# 3_circuito_logico_AND.net
KiCad netlist of a schematic drawn in EasyEDA Pro
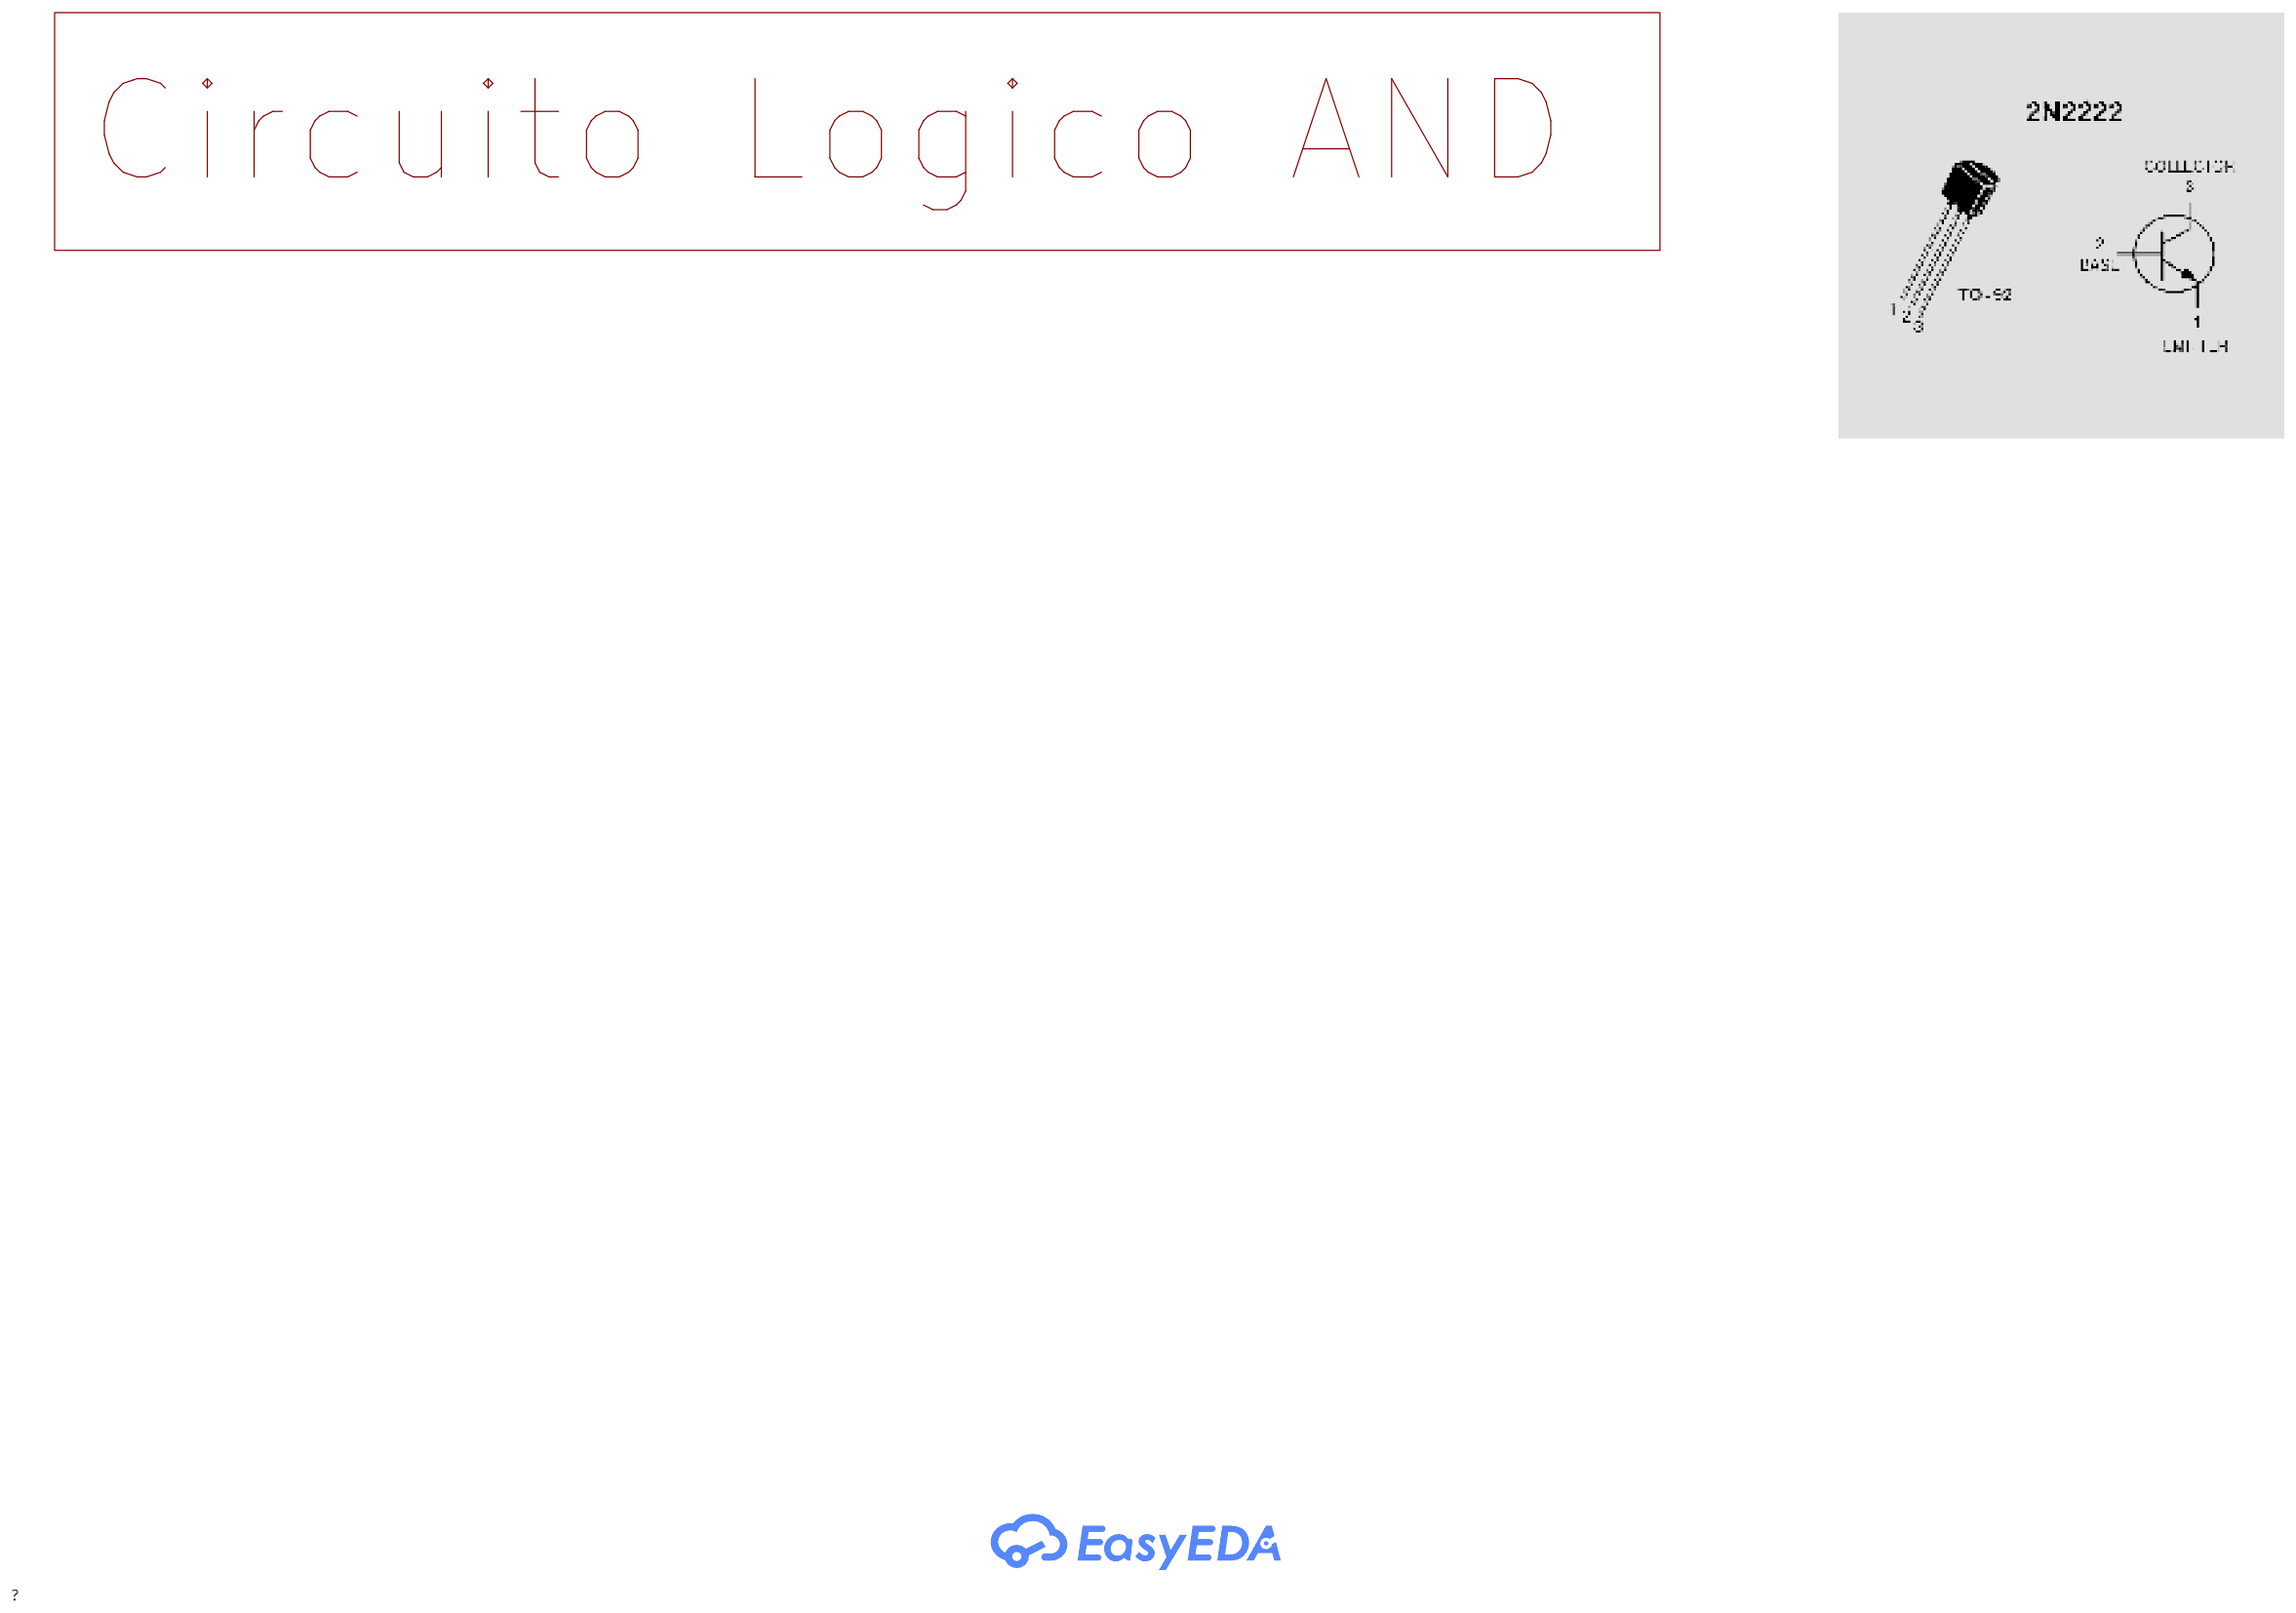
[diagram p0: P1]
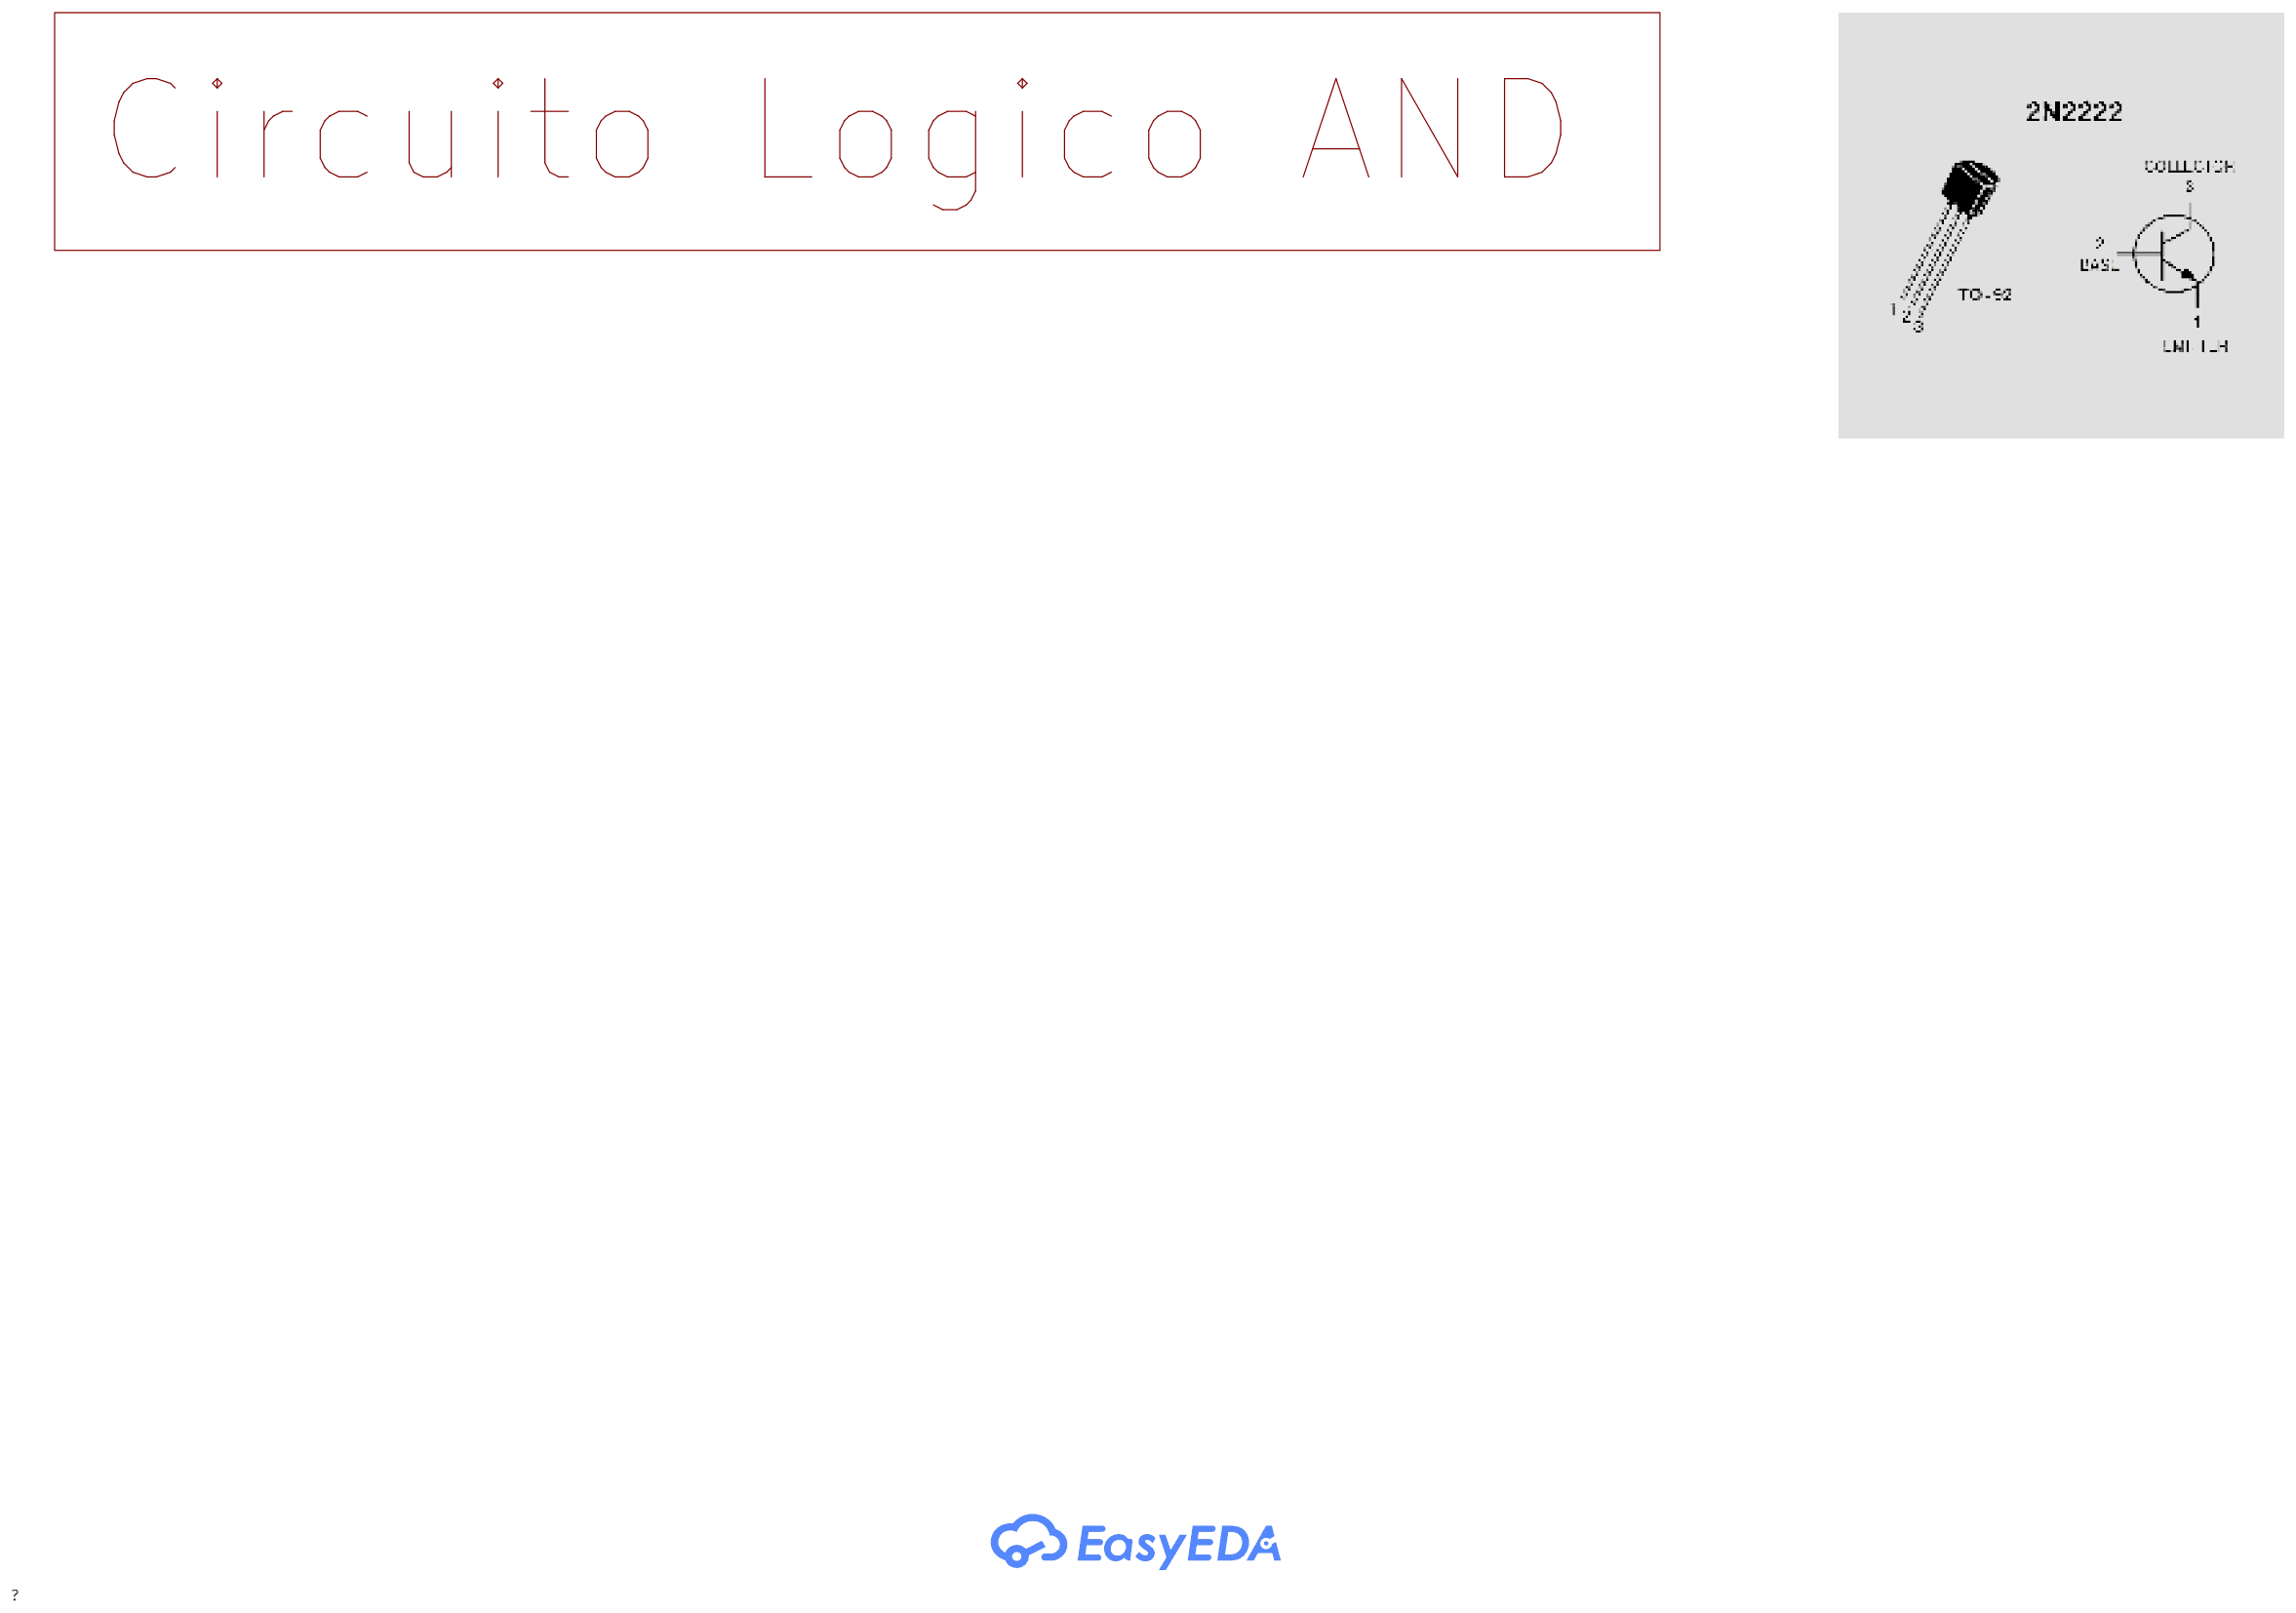
[diagram p1: P2]
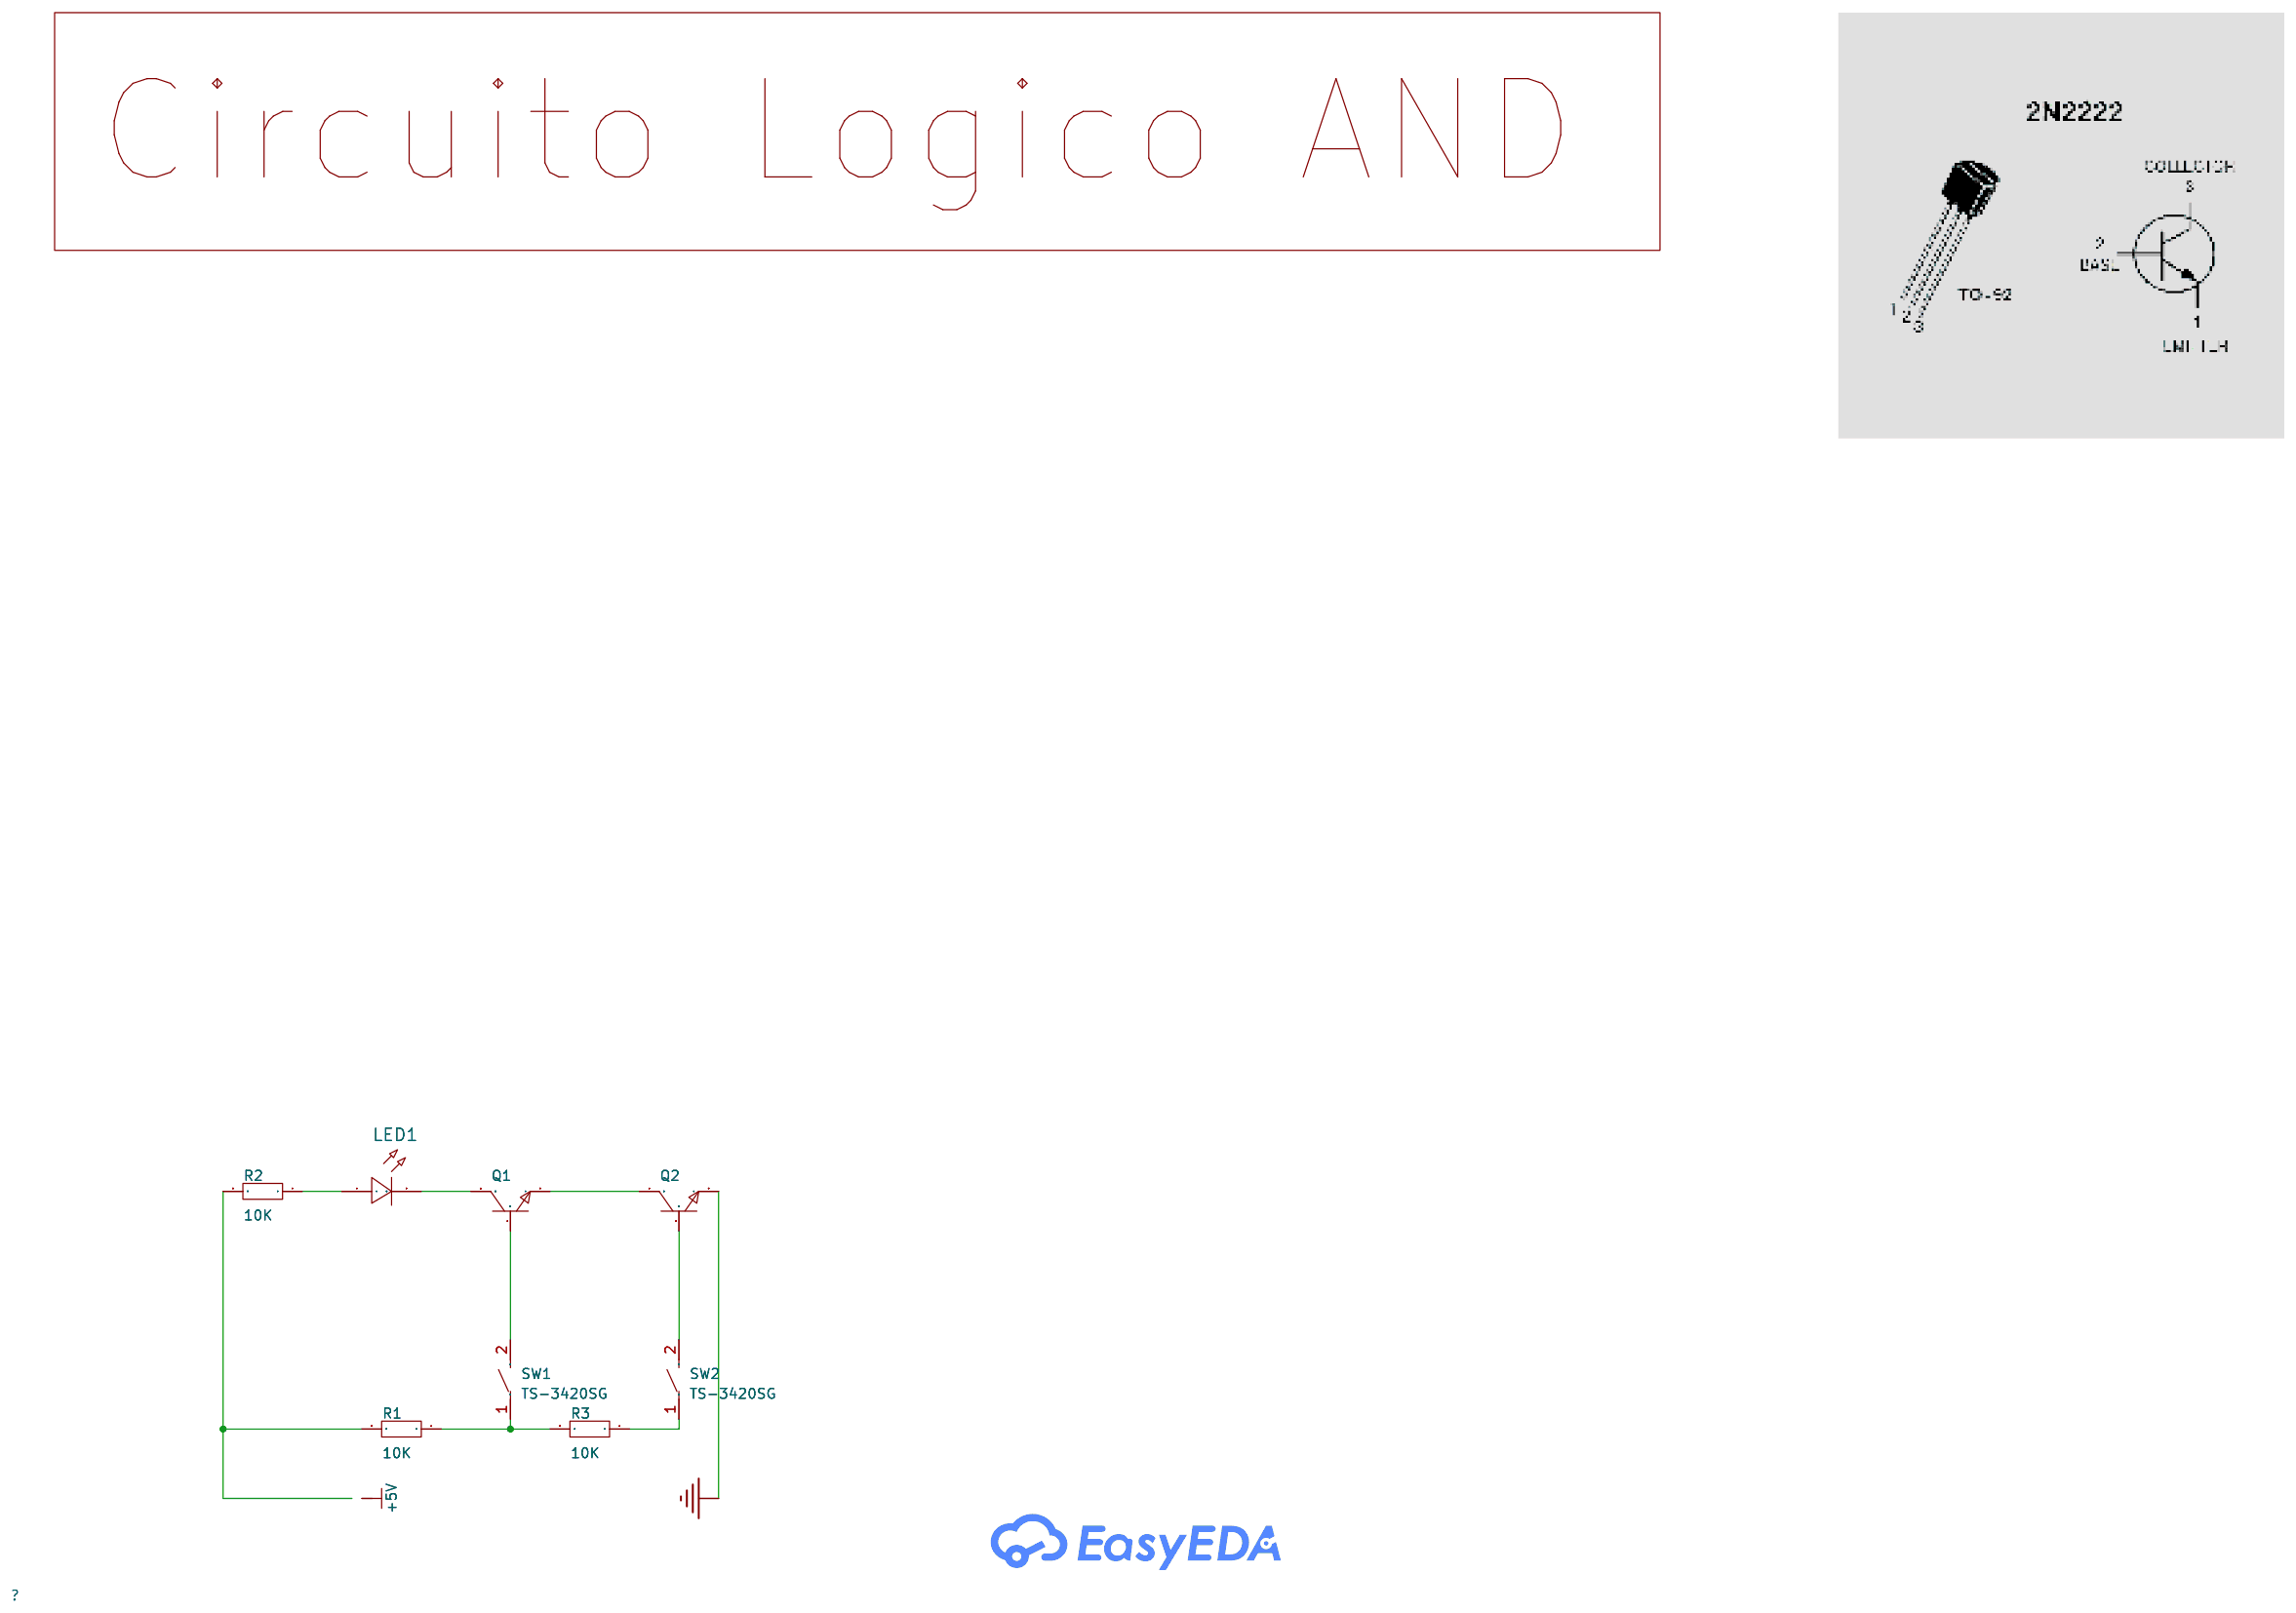
[diagram p2: P3]
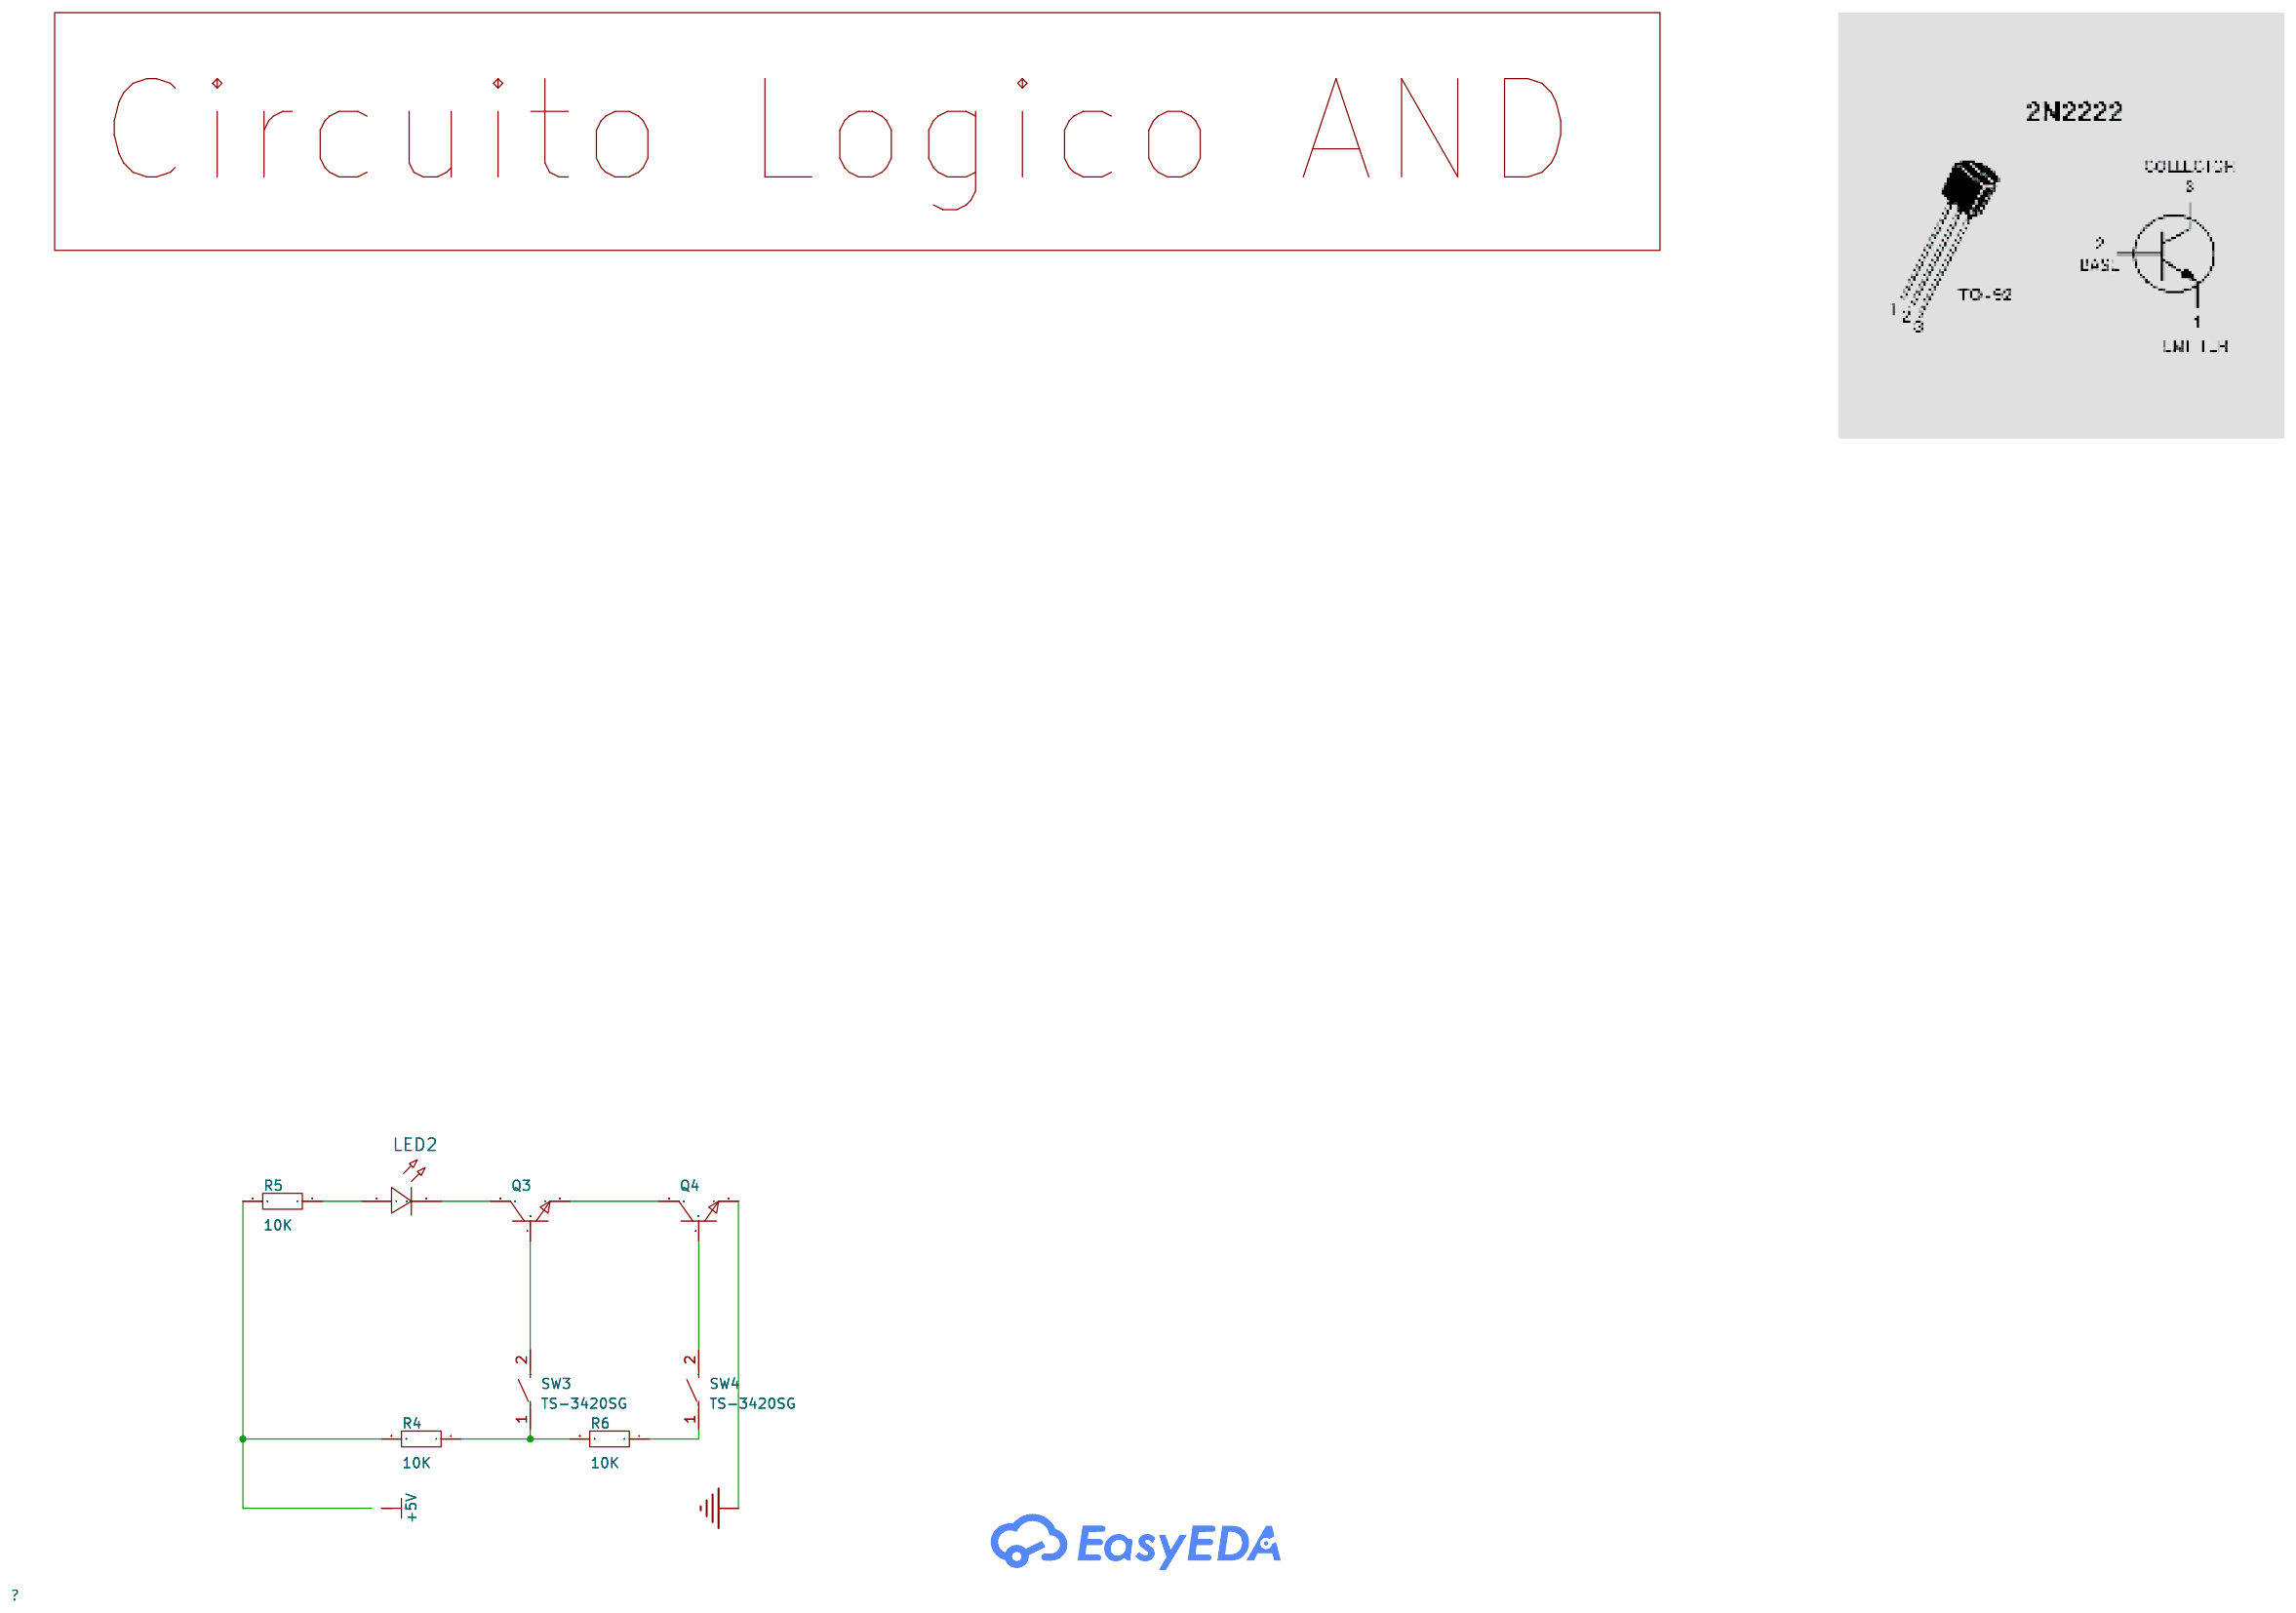
[diagram p3: P4]
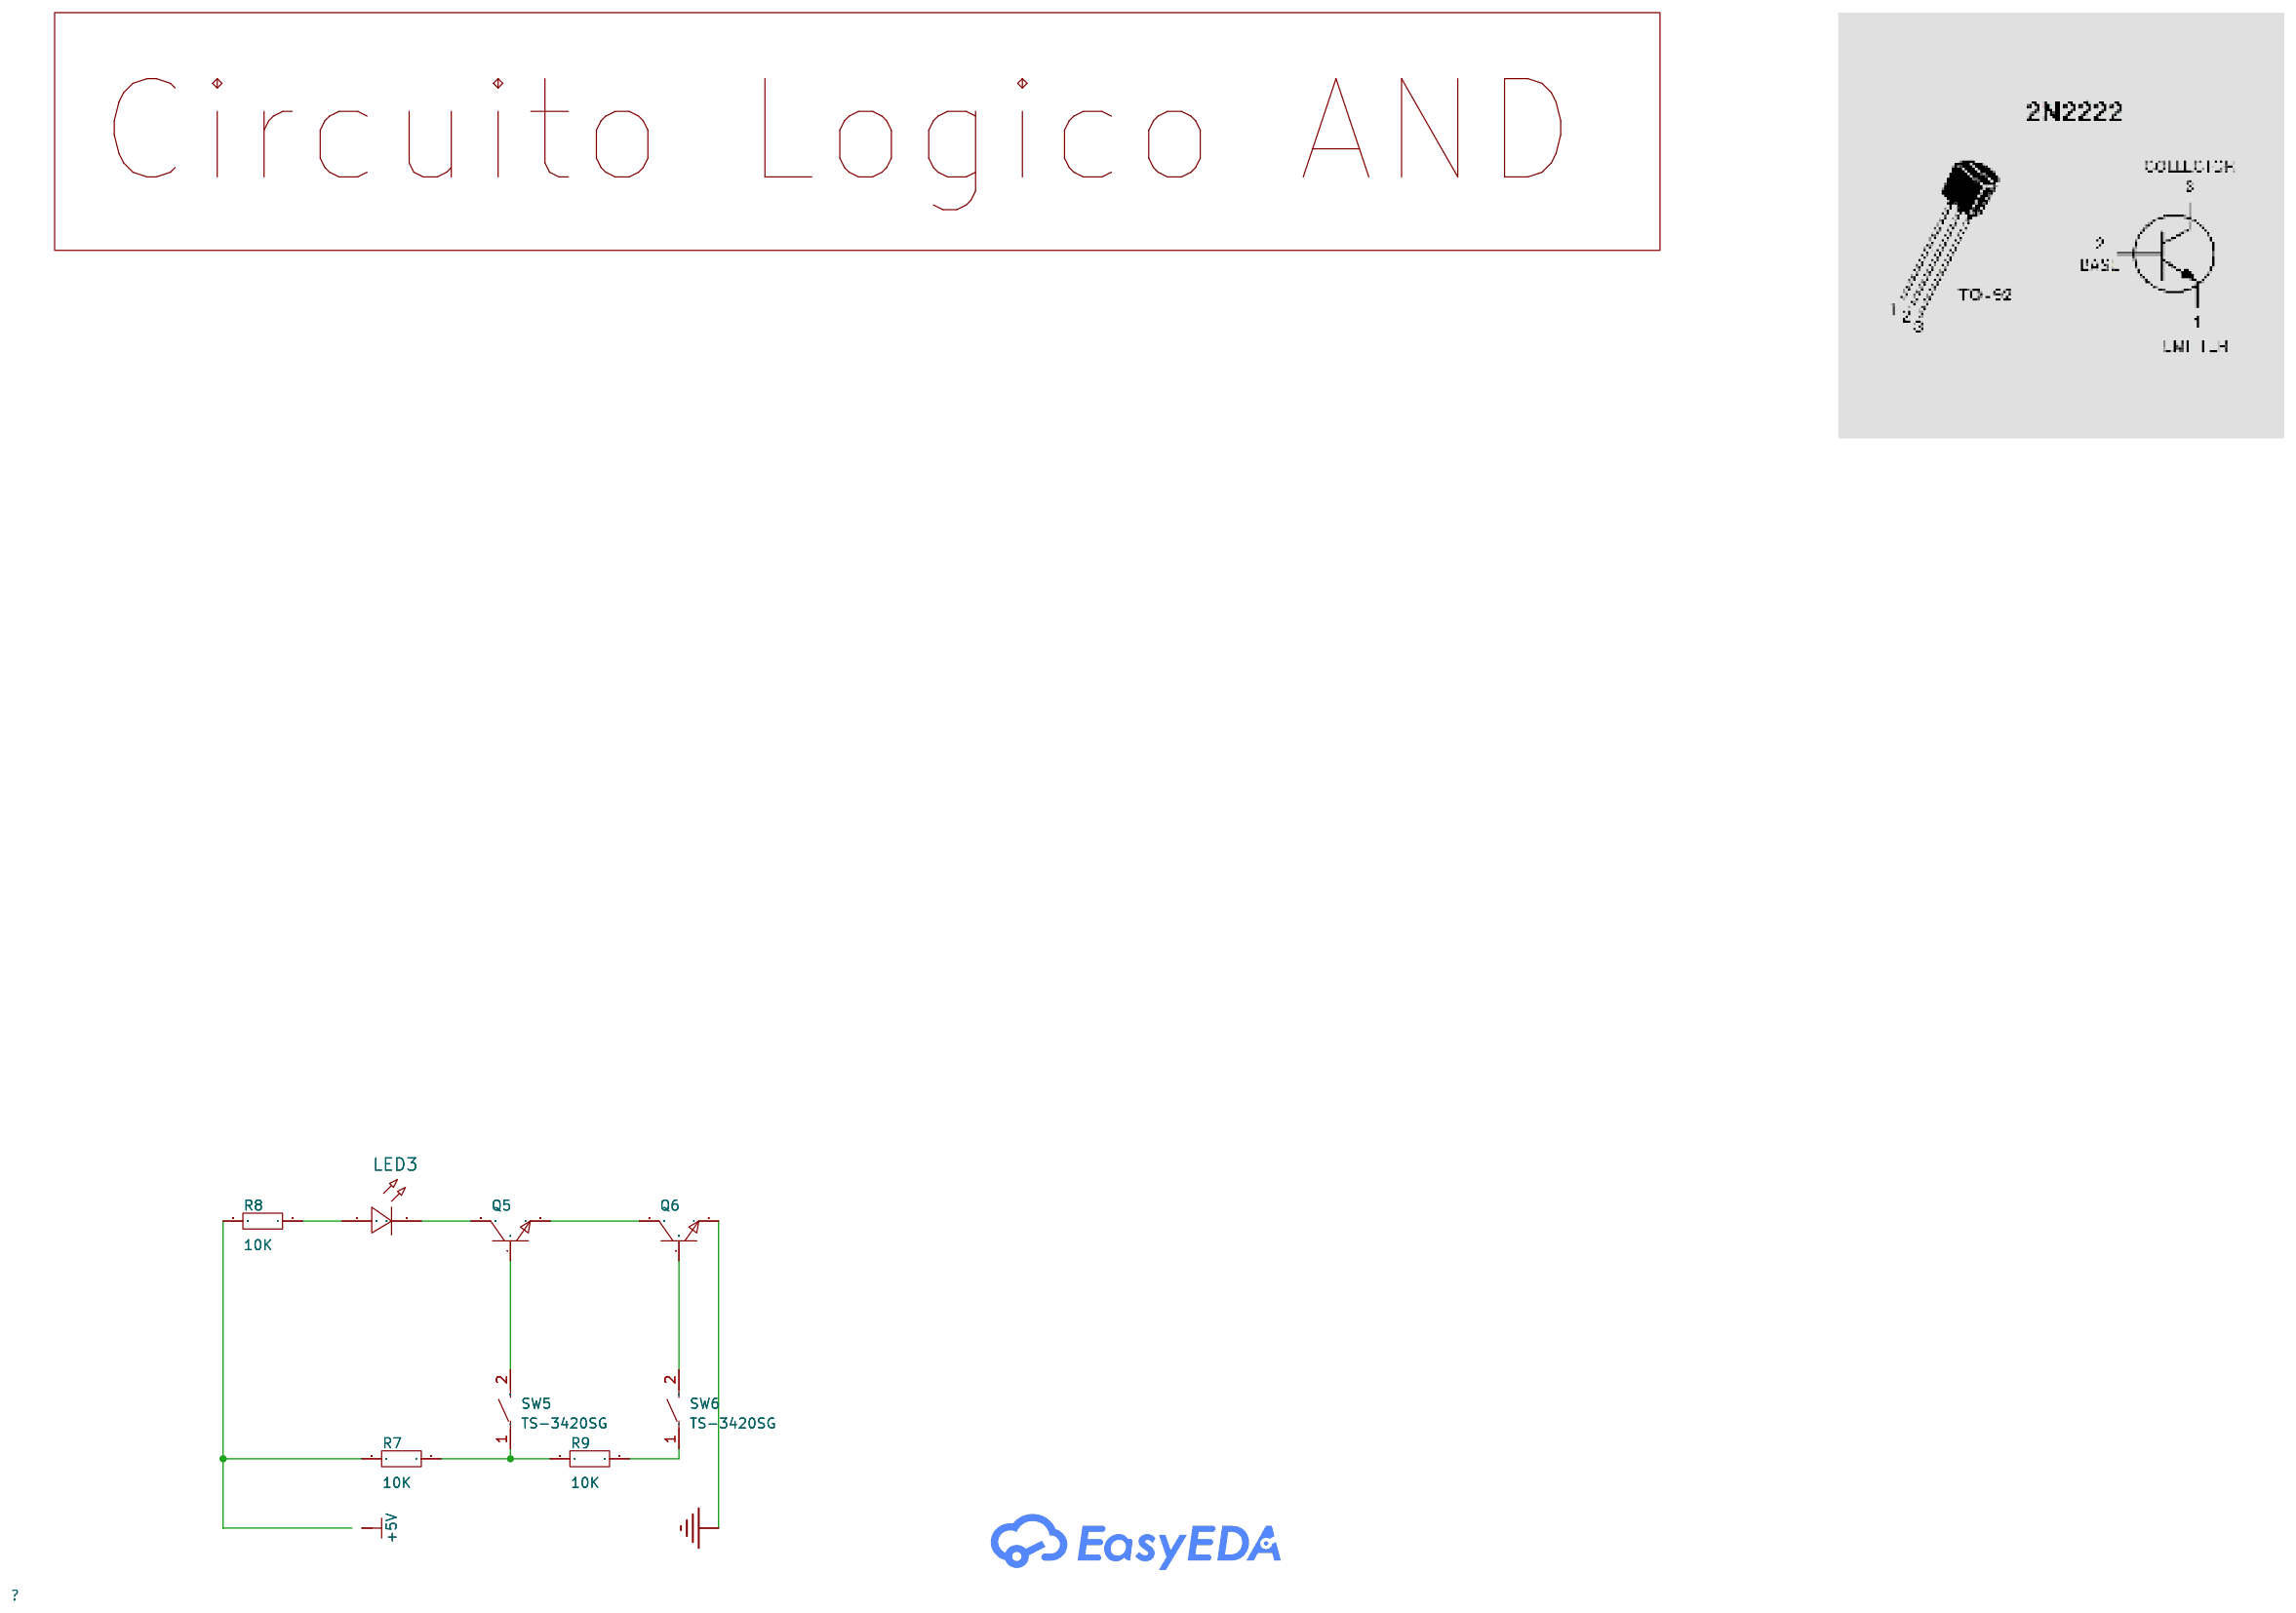
[diagram p4: P7]
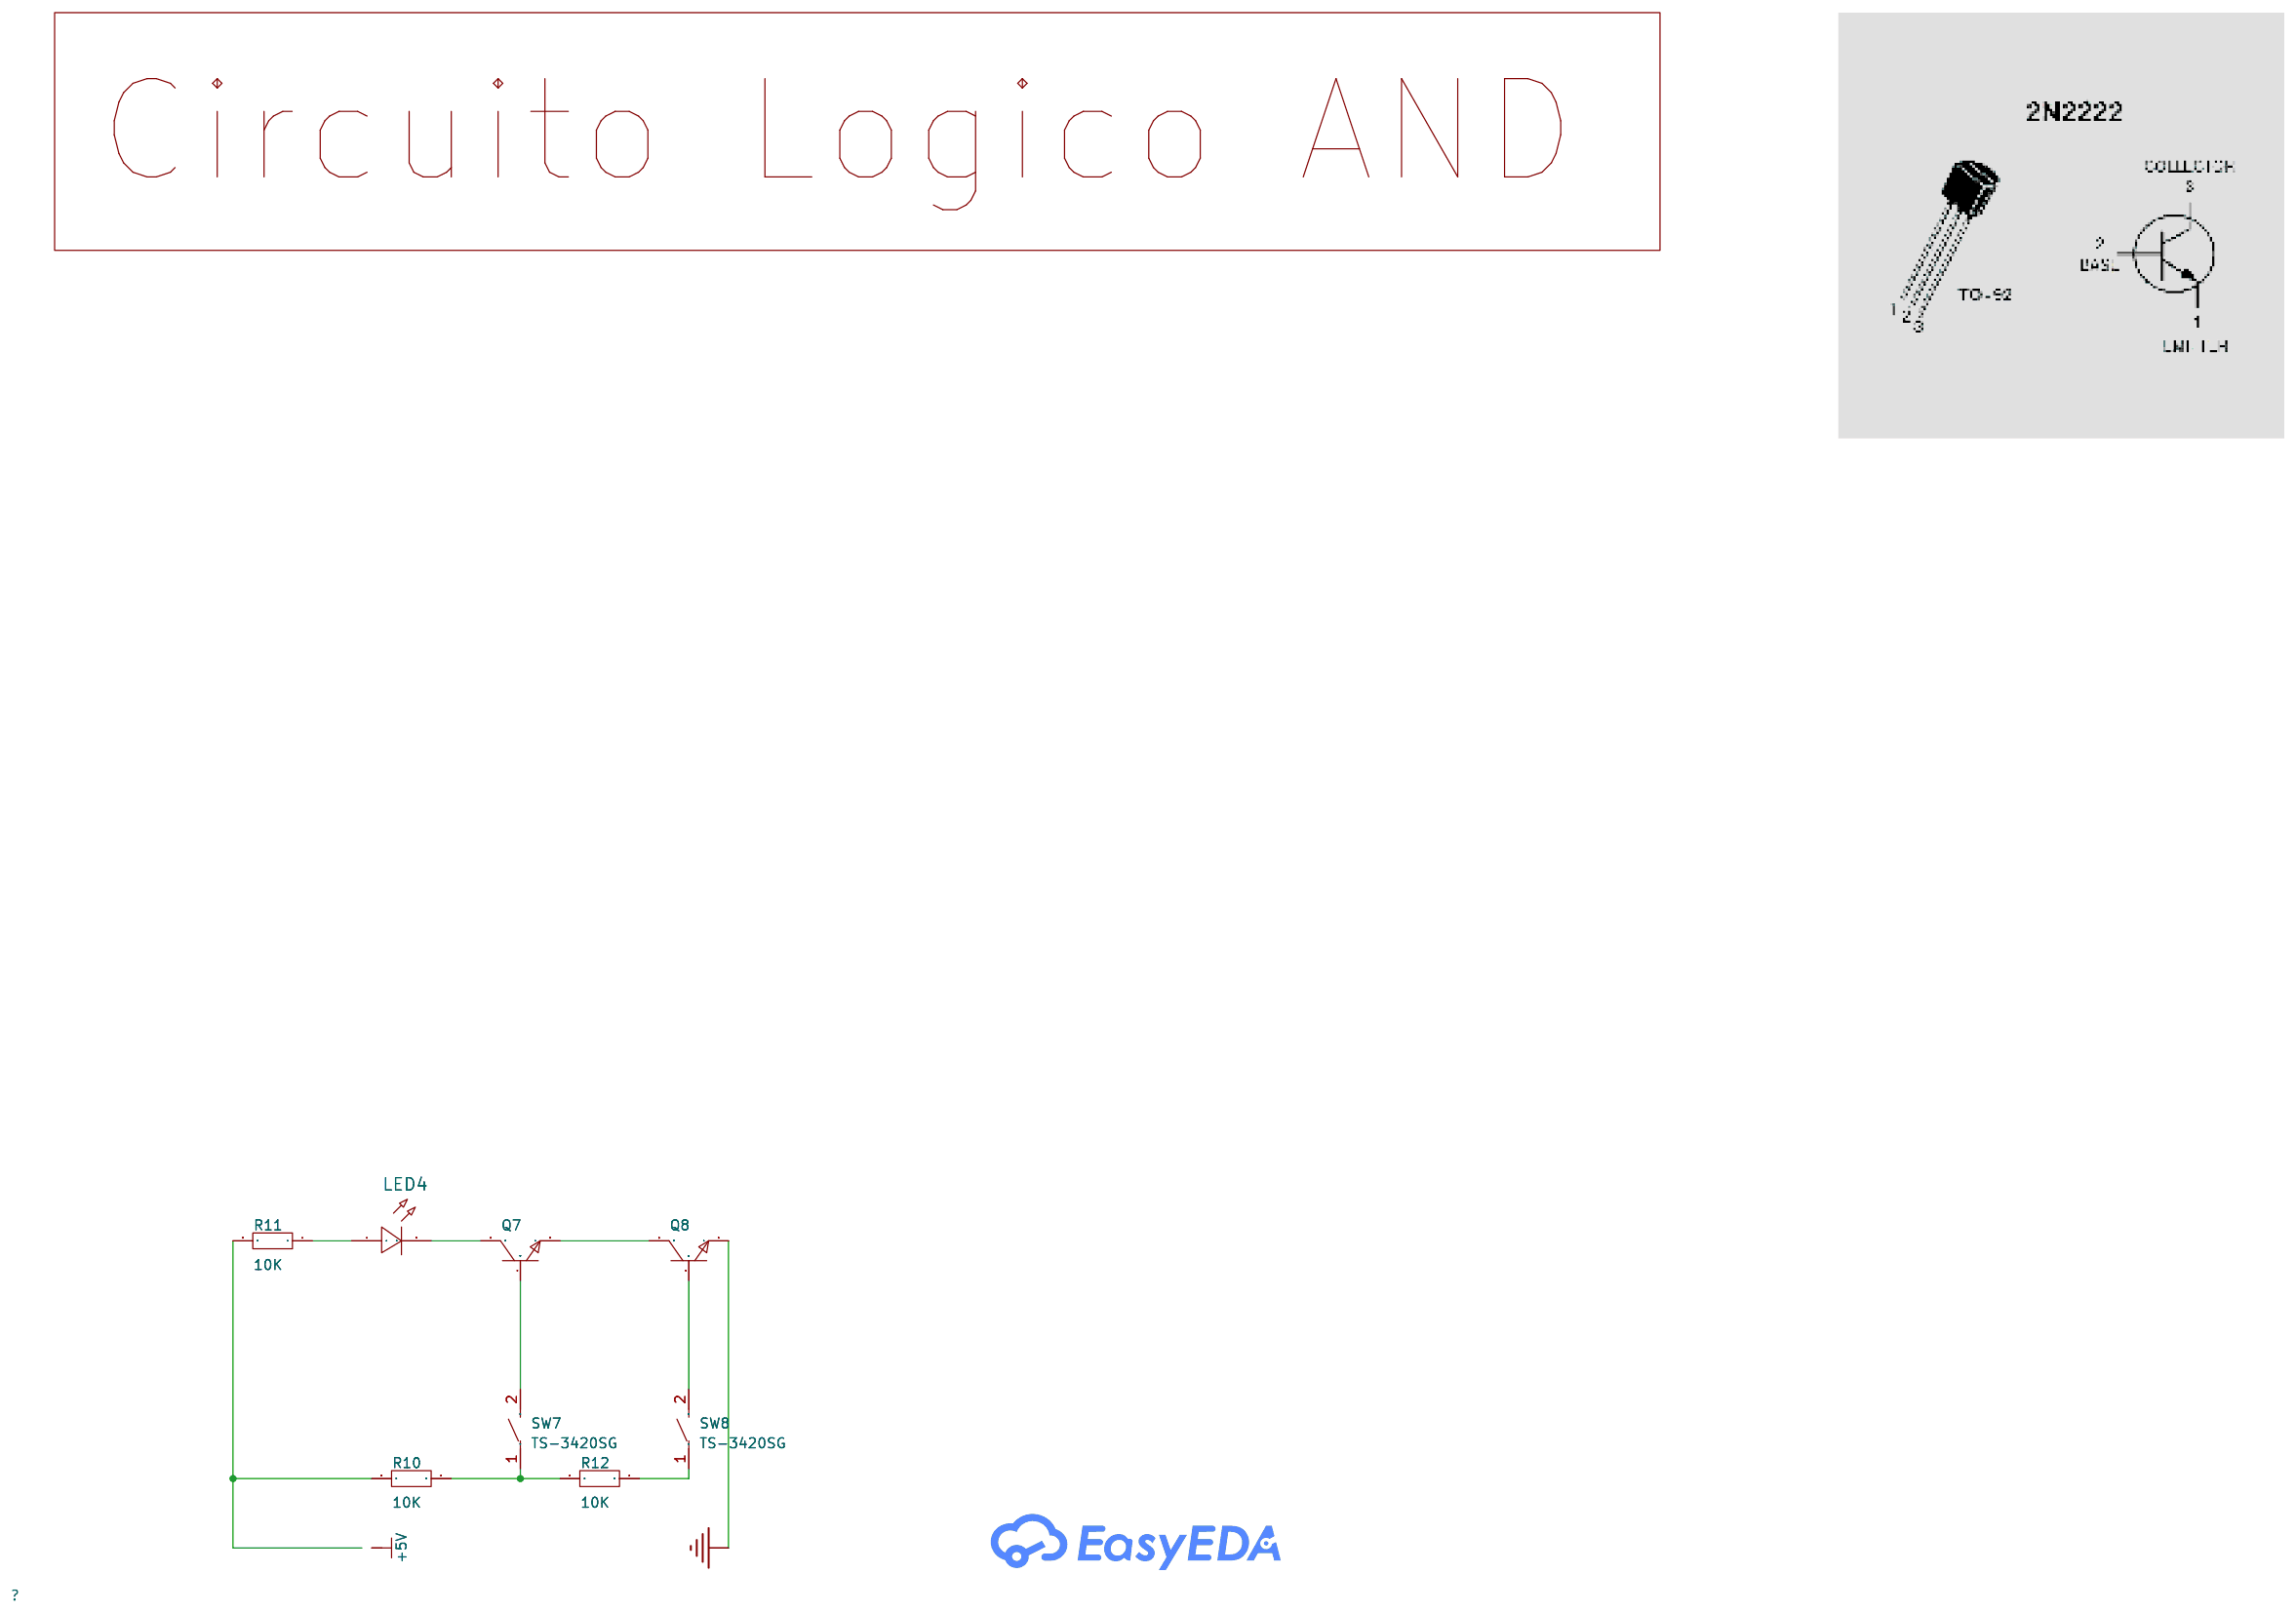
[diagram p5: P8]

(export (version "E")
  (design (tool "Eeschema 10.0.6"))
  (components
    (comp (ref "LED1")
      (value "~")
      (footprint "easyedapro:LED0402-RD_YELLOW")
      (libsource (lib "easyedapro") (part "LED_R"))
    )
    (comp (ref "Q1")
      (value "~")
      (footprint "easyedapro:TO-92-3_L4.9-W3.7-P1.27-L")
      (libsource (lib "easyedapro") (part "NPN"))
    )
    (comp (ref "Q2")
      (value "~")
      (footprint "easyedapro:TO-92-3_L4.9-W3.7-P1.27-L")
      (libsource (lib "easyedapro") (part "NPN"))
    )
    (comp (ref "R1") (value "10K") (footprint "easyedapro:R0603") (libsource (lib "easyedapro") (part "Res")))
    (comp (ref "R2") (value "10K") (footprint "easyedapro:R0603") (libsource (lib "easyedapro") (part "Res")))
    (comp (ref "R3") (value "10K") (footprint "easyedapro:R0603") (libsource (lib "easyedapro") (part "Res")))
    (comp (ref "SW1")
      (value "TS-3420SG")
      (footprint "easyedapro:SW-SMD_TS-3420SG")
      (fields (field (name "Manufacturer") "康深"))
      (libsource (lib "easyedapro") (part "TS-3420SG"))
    )
    (comp (ref "SW2")
      (value "TS-3420SG")
      (footprint "easyedapro:SW-SMD_TS-3420SG")
      (fields (field (name "Manufacturer") "康深"))
      (libsource (lib "easyedapro") (part "TS-3420SG"))
    )
    (comp (ref "LED2")
      (value "~")
      (footprint "easyedapro:LED0402-RD_YELLOW")
      (libsource (lib "easyedapro") (part "LED_R"))
    )
    (comp (ref "Q3")
      (value "~")
      (footprint "easyedapro:TO-92-3_L4.9-W3.7-P1.27-L")
      (libsource (lib "easyedapro") (part "NPN"))
    )
    (comp (ref "Q4")
      (value "~")
      (footprint "easyedapro:TO-92-3_L4.9-W3.7-P1.27-L")
      (libsource (lib "easyedapro") (part "NPN"))
    )
    (comp (ref "R4") (value "10K") (footprint "easyedapro:R0603") (libsource (lib "easyedapro") (part "Res")))
    (comp (ref "R5") (value "10K") (footprint "easyedapro:R0603") (libsource (lib "easyedapro") (part "Res")))
    (comp (ref "R6") (value "10K") (footprint "easyedapro:R0603") (libsource (lib "easyedapro") (part "Res")))
    (comp (ref "SW3")
      (value "TS-3420SG")
      (footprint "easyedapro:SW-SMD_TS-3420SG")
      (fields (field (name "Manufacturer") "康深"))
      (libsource (lib "easyedapro") (part "TS-3420SG"))
    )
    (comp (ref "SW4")
      (value "TS-3420SG")
      (footprint "easyedapro:SW-SMD_TS-3420SG")
      (fields (field (name "Manufacturer") "康深"))
      (libsource (lib "easyedapro") (part "TS-3420SG"))
    )
    (comp (ref "LED3")
      (value "~")
      (footprint "easyedapro:LED0402-RD_YELLOW")
      (libsource (lib "easyedapro") (part "LED_R"))
    )
    (comp (ref "Q5")
      (value "~")
      (footprint "easyedapro:TO-92-3_L4.9-W3.7-P1.27-L")
      (libsource (lib "easyedapro") (part "NPN"))
    )
    (comp (ref "Q6")
      (value "~")
      (footprint "easyedapro:TO-92-3_L4.9-W3.7-P1.27-L")
      (libsource (lib "easyedapro") (part "NPN"))
    )
    (comp (ref "R7") (value "10K") (footprint "easyedapro:R0603") (libsource (lib "easyedapro") (part "Res")))
    (comp (ref "R8") (value "10K") (footprint "easyedapro:R0603") (libsource (lib "easyedapro") (part "Res")))
    (comp (ref "R9") (value "10K") (footprint "easyedapro:R0603") (libsource (lib "easyedapro") (part "Res")))
    (comp (ref "SW5")
      (value "TS-3420SG")
      (footprint "easyedapro:SW-SMD_TS-3420SG")
      (fields (field (name "Manufacturer") "康深"))
      (libsource (lib "easyedapro") (part "TS-3420SG"))
    )
    (comp (ref "SW6")
      (value "TS-3420SG")
      (footprint "easyedapro:SW-SMD_TS-3420SG")
      (fields (field (name "Manufacturer") "康深"))
      (libsource (lib "easyedapro") (part "TS-3420SG"))
    )
    (comp (ref "LED4")
      (value "~")
      (footprint "easyedapro:LED0402-RD_YELLOW")
      (libsource (lib "easyedapro") (part "LED_R"))
    )
    (comp (ref "Q7")
      (value "~")
      (footprint "easyedapro:TO-92-3_L4.9-W3.7-P1.27-L")
      (libsource (lib "easyedapro") (part "NPN"))
    )
    (comp (ref "Q8")
      (value "~")
      (footprint "easyedapro:TO-92-3_L4.9-W3.7-P1.27-L")
      (libsource (lib "easyedapro") (part "NPN"))
    )
    (comp (ref "R10")
      (value "10K")
      (footprint "easyedapro:R0603")
      (libsource (lib "easyedapro") (part "Res"))
    )
    (comp (ref "R11")
      (value "10K")
      (footprint "easyedapro:R0603")
      (libsource (lib "easyedapro") (part "Res"))
    )
    (comp (ref "R12")
      (value "10K")
      (footprint "easyedapro:R0603")
      (libsource (lib "easyedapro") (part "Res"))
    )
    (comp (ref "SW7")
      (value "TS-3420SG")
      (footprint "easyedapro:SW-SMD_TS-3420SG")
      (fields (field (name "Manufacturer") "康深"))
      (libsource (lib "easyedapro") (part "TS-3420SG"))
    )
    (comp (ref "SW8")
      (value "TS-3420SG")
      (footprint "easyedapro:SW-SMD_TS-3420SG")
      (fields (field (name "Manufacturer") "康深"))
      (libsource (lib "easyedapro") (part "TS-3420SG"))
    )
  )
  (nets
    (net (code "2") (name "GND") (class "Default")
      (node (ref "Q2") (pin "2") (pinfunction "E_2") (pintype "unspecified"))
      (node (ref "Q4") (pin "2") (pinfunction "E_2") (pintype "unspecified"))
      (node (ref "Q6") (pin "2") (pinfunction "E_2") (pintype "unspecified"))
      (node (ref "Q8") (pin "2") (pinfunction "E_2") (pintype "unspecified"))
    )
    (net (code "3") (name "Net-(LED1-A)") (class "Default")
      (node (ref "LED1") (pin "1") (pinfunction "A_1") (pintype "input"))
      (node (ref "R2") (pin "1") (pinfunction "1_1") (pintype "input"))
    )
    (net (code "4") (name "Net-(LED1-C)") (class "Default")
      (node (ref "LED1") (pin "2") (pinfunction "C_2") (pintype "input"))
      (node (ref "Q1") (pin "3") (pinfunction "C_3") (pintype "unspecified"))
    )
    (net (code "5") (name "Net-(LED2-A)") (class "Default")
      (node (ref "LED2") (pin "1") (pinfunction "A_1") (pintype "input"))
      (node (ref "R5") (pin "1") (pinfunction "1_1") (pintype "input"))
    )
    (net (code "6") (name "Net-(LED2-C)") (class "Default")
      (node (ref "LED2") (pin "2") (pinfunction "C_2") (pintype "input"))
      (node (ref "Q3") (pin "3") (pinfunction "C_3") (pintype "unspecified"))
    )
    (net (code "7") (name "Net-(LED3-A)") (class "Default")
      (node (ref "LED3") (pin "1") (pinfunction "A_1") (pintype "input"))
      (node (ref "R8") (pin "1") (pinfunction "1_1") (pintype "input"))
    )
    (net (code "8") (name "Net-(LED3-C)") (class "Default")
      (node (ref "LED3") (pin "2") (pinfunction "C_2") (pintype "input"))
      (node (ref "Q5") (pin "3") (pinfunction "C_3") (pintype "unspecified"))
    )
    (net (code "9") (name "Net-(LED4-A)") (class "Default")
      (node (ref "LED4") (pin "1") (pinfunction "A_1") (pintype "input"))
      (node (ref "R11") (pin "1") (pinfunction "1_1") (pintype "input"))
    )
    (net (code "10") (name "Net-(LED4-C)") (class "Default")
      (node (ref "LED4") (pin "2") (pinfunction "C_2") (pintype "input"))
      (node (ref "Q7") (pin "3") (pinfunction "C_3") (pintype "unspecified"))
    )
    (net (code "11") (name "Net-(Q1-B)") (class "Default")
      (node (ref "Q1") (pin "1") (pinfunction "B_1") (pintype "unspecified"))
      (node (ref "SW1") (pin "2") (pinfunction "2_2") (pintype "unspecified"))
    )
    (net (code "12") (name "Net-(Q1-E)") (class "Default")
      (node (ref "Q1") (pin "2") (pinfunction "E_2") (pintype "unspecified"))
      (node (ref "Q2") (pin "3") (pinfunction "C_3") (pintype "unspecified"))
    )
    (net (code "13") (name "Net-(Q2-B)") (class "Default")
      (node (ref "Q2") (pin "1") (pinfunction "B_1") (pintype "unspecified"))
      (node (ref "SW2") (pin "2") (pinfunction "2_2") (pintype "unspecified"))
    )
    (net (code "14") (name "Net-(Q3-B)") (class "Default")
      (node (ref "Q3") (pin "1") (pinfunction "B_1") (pintype "unspecified"))
      (node (ref "SW3") (pin "2") (pinfunction "2_2") (pintype "unspecified"))
    )
    (net (code "15") (name "Net-(Q3-E)") (class "Default")
      (node (ref "Q3") (pin "2") (pinfunction "E_2") (pintype "unspecified"))
      (node (ref "Q4") (pin "3") (pinfunction "C_3") (pintype "unspecified"))
    )
    (net (code "16") (name "Net-(Q4-B)") (class "Default")
      (node (ref "Q4") (pin "1") (pinfunction "B_1") (pintype "unspecified"))
      (node (ref "SW4") (pin "2") (pinfunction "2_2") (pintype "unspecified"))
    )
    (net (code "17") (name "Net-(Q5-B)") (class "Default")
      (node (ref "Q5") (pin "1") (pinfunction "B_1") (pintype "unspecified"))
      (node (ref "SW5") (pin "2") (pinfunction "2_2") (pintype "unspecified"))
    )
    (net (code "18") (name "Net-(Q5-E)") (class "Default")
      (node (ref "Q5") (pin "2") (pinfunction "E_2") (pintype "unspecified"))
      (node (ref "Q6") (pin "3") (pinfunction "C_3") (pintype "unspecified"))
    )
    (net (code "19") (name "Net-(Q6-B)") (class "Default")
      (node (ref "Q6") (pin "1") (pinfunction "B_1") (pintype "unspecified"))
      (node (ref "SW6") (pin "2") (pinfunction "2_2") (pintype "unspecified"))
    )
    (net (code "20") (name "Net-(Q7-B)") (class "Default")
      (node (ref "Q7") (pin "1") (pinfunction "B_1") (pintype "unspecified"))
      (node (ref "SW7") (pin "2") (pinfunction "2_2") (pintype "unspecified"))
    )
    (net (code "21") (name "Net-(Q7-E)") (class "Default")
      (node (ref "Q7") (pin "2") (pinfunction "E_2") (pintype "unspecified"))
      (node (ref "Q8") (pin "3") (pinfunction "C_3") (pintype "unspecified"))
    )
    (net (code "22") (name "Net-(Q8-B)") (class "Default")
      (node (ref "Q8") (pin "1") (pinfunction "B_1") (pintype "unspecified"))
      (node (ref "SW8") (pin "2") (pinfunction "2_2") (pintype "unspecified"))
    )
    (net (code "23") (name "Net-(R1-Pad1)") (class "Default")
      (node (ref "R1") (pin "1") (pinfunction "1_1") (pintype "input"))
      (node (ref "R3") (pin "2") (pinfunction "2_2") (pintype "input"))
      (node (ref "SW1") (pin "1") (pinfunction "1_1") (pintype "unspecified"))
    )
    (net (code "24") (name "Net-(R1-Pad2)") (class "Default")
      (node (ref "R1") (pin "2") (pinfunction "2_2") (pintype "input"))
      (node (ref "R2") (pin "2") (pinfunction "2_2") (pintype "input"))
    )
    (net (code "25") (name "Net-(R3-Pad1)") (class "Default")
      (node (ref "R3") (pin "1") (pinfunction "1_1") (pintype "input"))
      (node (ref "SW2") (pin "1") (pinfunction "1_1") (pintype "unspecified"))
    )
    (net (code "26") (name "Net-(R4-Pad1)") (class "Default")
      (node (ref "R4") (pin "1") (pinfunction "1_1") (pintype "input"))
      (node (ref "R6") (pin "2") (pinfunction "2_2") (pintype "input"))
      (node (ref "SW3") (pin "1") (pinfunction "1_1") (pintype "unspecified"))
    )
    (net (code "27") (name "Net-(R4-Pad2)") (class "Default")
      (node (ref "R4") (pin "2") (pinfunction "2_2") (pintype "input"))
      (node (ref "R5") (pin "2") (pinfunction "2_2") (pintype "input"))
    )
    (net (code "28") (name "Net-(R6-Pad1)") (class "Default")
      (node (ref "R6") (pin "1") (pinfunction "1_1") (pintype "input"))
      (node (ref "SW4") (pin "1") (pinfunction "1_1") (pintype "unspecified"))
    )
    (net (code "29") (name "Net-(R7-Pad1)") (class "Default")
      (node (ref "R7") (pin "1") (pinfunction "1_1") (pintype "input"))
      (node (ref "R9") (pin "2") (pinfunction "2_2") (pintype "input"))
      (node (ref "SW5") (pin "1") (pinfunction "1_1") (pintype "unspecified"))
    )
    (net (code "30") (name "Net-(R7-Pad2)") (class "Default")
      (node (ref "R7") (pin "2") (pinfunction "2_2") (pintype "input"))
      (node (ref "R8") (pin "2") (pinfunction "2_2") (pintype "input"))
    )
    (net (code "31") (name "Net-(R9-Pad1)") (class "Default")
      (node (ref "R9") (pin "1") (pinfunction "1_1") (pintype "input"))
      (node (ref "SW6") (pin "1") (pinfunction "1_1") (pintype "unspecified"))
    )
    (net (code "32") (name "Net-(R10-Pad1)") (class "Default")
      (node (ref "R10") (pin "1") (pinfunction "1_1") (pintype "input"))
      (node (ref "R12") (pin "2") (pinfunction "2_2") (pintype "input"))
      (node (ref "SW7") (pin "1") (pinfunction "1_1") (pintype "unspecified"))
    )
    (net (code "33") (name "Net-(R10-Pad2)") (class "Default")
      (node (ref "R10") (pin "2") (pinfunction "2_2") (pintype "input"))
      (node (ref "R11") (pin "2") (pinfunction "2_2") (pintype "input"))
    )
    (net (code "34") (name "Net-(R12-Pad1)") (class "Default")
      (node (ref "R12") (pin "1") (pinfunction "1_1") (pintype "input"))
      (node (ref "SW8") (pin "1") (pinfunction "1_1") (pintype "unspecified"))
    )
  )
)
